# Fuse.net
KiCad netlist of a schematic drawn in Altium Designer
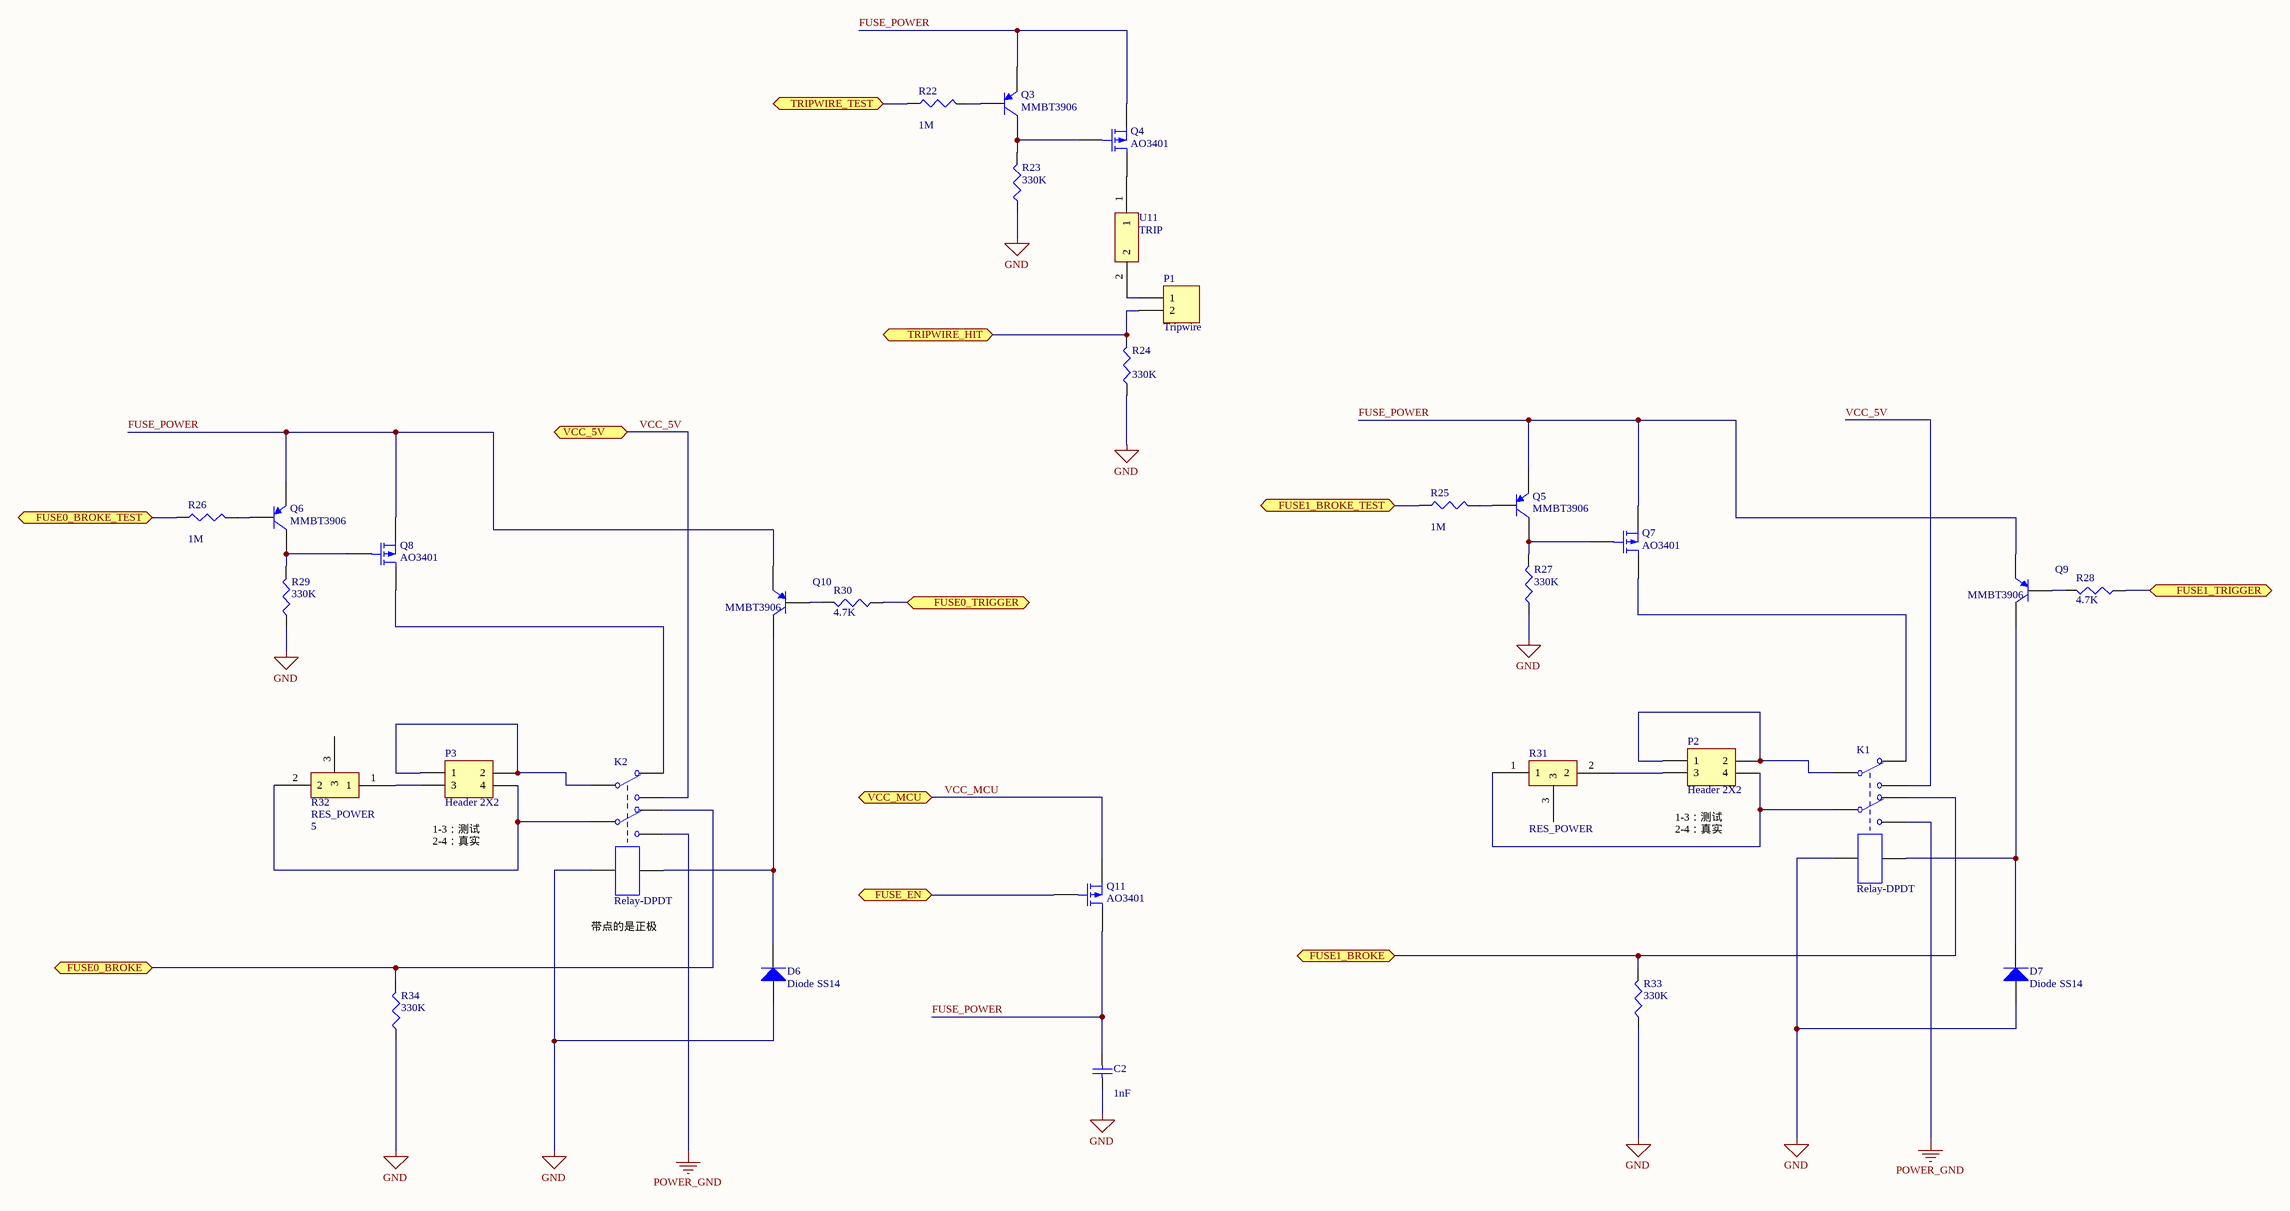
[diagram p0: Fuse.SchDoc]

(export (version "E")
  (design (tool "Eeschema 10.0.6"))
  (components
    (comp (ref "C2")
      (value "1nF")
      (footprint "clock:0603")
      (description "Capacitor (Semiconductor SIM Model)")
      (fields (field (name "Comment") "Cap Semi") (field (name "PUBLISHER") "Altium Limited"))
      (libsource (lib "Miscellaneous Devices") (part "Cap Semi"))
    )
    (comp (ref "D6")
      (value "Diode SS14")
      (footprint "clock:SMA")
      (description "1 Amp General Purpose Rectifier")
      (fields (field (name "PUBLISHER") "Altium Limited"))
      (libsource (lib "Miscellaneous Devices") (part "Diode 1N4005"))
    )
    (comp (ref "D7")
      (value "Diode SS14")
      (footprint "clock:SMA")
      (description "1 Amp General Purpose Rectifier")
      (fields (field (name "PUBLISHER") "Altium Limited"))
      (libsource (lib "Miscellaneous Devices") (part "Diode 1N4005"))
    )
    (comp (ref "K1")
      (value "Relay-DPDT")
      (footprint "clock:G6K2PY")
      (description "Dual-Pole Dual-Throw Relay")
      (fields (field (name "PUBLISHER") "Altium Limited"))
      (libsource (lib "Miscellaneous Devices") (part "Relay-DPDT"))
    )
    (comp (ref "K2")
      (value "Relay-DPDT")
      (footprint "clock:G6K2PY")
      (description "Dual-Pole Dual-Throw Relay")
      (fields (field (name "PUBLISHER") "Altium Limited"))
      (libsource (lib "Miscellaneous Devices") (part "Relay-DPDT"))
    )
    (comp (ref "P1")
      (value "Tripwire")
      (footprint "HDR1X2")
      (description "Header, 2-Pin")
      (fields (field (name "PUBLISHER") "Altium Limited"))
      (libsource (lib "Miscellaneous Connectors") (part "Header 2"))
    )
    (comp (ref "P2")
      (value "Header 2X2")
      (footprint "clock:HDR2X2")
      (description "Header, 2-Pin, Dual row")
      (fields (field (name "PUBLISHER") "Altium Limited"))
      (libsource (lib "Miscellaneous Connectors") (part "Header 2X2"))
    )
    (comp (ref "P3")
      (value "Header 2X2")
      (footprint "clock:HDR2X2")
      (description "Header, 2-Pin, Dual row")
      (fields (field (name "PUBLISHER") "Altium Limited"))
      (libsource (lib "Miscellaneous Connectors") (part "Header 2X2"))
    )
    (comp (ref "Q3")
      (value "MMBT3906")
      (footprint "clock:SOT23-3-PNP")
      (description "PNP Bipolar Transistor")
      (fields (field (name "PUBLISHER") "Altium Limited"))
      (libsource (lib "Miscellaneous Devices") (part "PNP"))
    )
    (comp (ref "Q4")
      (value "AO3401")
      (footprint "clock:SOT23-3-PMOS")
      (description "P-Channel MOSFET")
      (fields (field (name "PUBLISHER") "Altium Limited"))
      (libsource (lib "Miscellaneous Devices") (part "MOSFET-P"))
    )
    (comp (ref "Q5")
      (value "MMBT3906")
      (footprint "clock:SOT23-3-PNP")
      (description "PNP Bipolar Transistor")
      (fields (field (name "PUBLISHER") "Altium Limited"))
      (libsource (lib "Miscellaneous Devices") (part "PNP"))
    )
    (comp (ref "Q6")
      (value "MMBT3906")
      (footprint "clock:SOT23-3-PNP")
      (description "PNP Bipolar Transistor")
      (fields (field (name "PUBLISHER") "Altium Limited"))
      (libsource (lib "Miscellaneous Devices") (part "PNP"))
    )
    (comp (ref "Q7")
      (value "AO3401")
      (footprint "clock:SOT23-3-PMOS")
      (description "P-Channel MOSFET")
      (fields (field (name "PUBLISHER") "Altium Limited"))
      (libsource (lib "Miscellaneous Devices") (part "MOSFET-P"))
    )
    (comp (ref "Q8")
      (value "AO3401")
      (footprint "clock:SOT23-3-PMOS")
      (description "P-Channel MOSFET")
      (fields (field (name "PUBLISHER") "Altium Limited"))
      (libsource (lib "Miscellaneous Devices") (part "MOSFET-P"))
    )
    (comp (ref "Q9")
      (value "MMBT3906")
      (footprint "clock:SOT23-3-PNP")
      (description "PNP Bipolar Transistor")
      (fields (field (name "PUBLISHER") "Altium Limited"))
      (libsource (lib "Miscellaneous Devices") (part "PNP"))
    )
    (comp (ref "Q10")
      (value "MMBT3906")
      (footprint "clock:SOT23-3-PNP")
      (description "PNP Bipolar Transistor")
      (fields (field (name "PUBLISHER") "Altium Limited"))
      (libsource (lib "Miscellaneous Devices") (part "PNP"))
    )
    (comp (ref "Q11")
      (value "AO3401")
      (footprint "clock:SOT23-3-PMOS")
      (description "P-Channel MOSFET")
      (fields (field (name "PUBLISHER") "Altium Limited"))
      (libsource (lib "Miscellaneous Devices") (part "MOSFET-P"))
    )
    (comp (ref "R22")
      (value "1M")
      (footprint "clock:0603")
      (description "Resistor")
      (fields (field (name "Comment") "Res3") (field (name "PUBLISHER") "Altium Limited"))
      (libsource (lib "Miscellaneous Devices") (part "Res3"))
    )
    (comp (ref "R23")
      (value "330K")
      (footprint "clock:0603")
      (description "Resistor")
      (fields (field (name "Comment") "Res3") (field (name "PUBLISHER") "Altium Limited"))
      (libsource (lib "Miscellaneous Devices") (part "Res3"))
    )
    (comp (ref "R24")
      (value "330K")
      (footprint "clock:0603")
      (description "Resistor")
      (fields (field (name "Comment") "Res3") (field (name "PUBLISHER") "Altium Limited"))
      (libsource (lib "Miscellaneous Devices") (part "Res3"))
    )
    (comp (ref "R25")
      (value "1M")
      (footprint "clock:0603")
      (description "Resistor")
      (fields (field (name "Comment") "Res3") (field (name "PUBLISHER") "Altium Limited"))
      (libsource (lib "Miscellaneous Devices") (part "Res3"))
    )
    (comp (ref "R26")
      (value "1M")
      (footprint "clock:0603")
      (description "Resistor")
      (fields (field (name "Comment") "Res3") (field (name "PUBLISHER") "Altium Limited"))
      (libsource (lib "Miscellaneous Devices") (part "Res3"))
    )
    (comp (ref "R27")
      (value "330K")
      (footprint "clock:0603")
      (description "Resistor")
      (fields (field (name "Comment") "Res3") (field (name "PUBLISHER") "Altium Limited"))
      (libsource (lib "Miscellaneous Devices") (part "Res3"))
    )
    (comp (ref "R28")
      (value "4.7K")
      (footprint "clock:0603")
      (description "Resistor")
      (fields (field (name "Comment") "Res3") (field (name "PUBLISHER") "Altium Limited"))
      (libsource (lib "Miscellaneous Devices") (part "Res3"))
    )
    (comp (ref "R29")
      (value "330K")
      (footprint "clock:0603")
      (description "Resistor")
      (fields (field (name "Comment") "Res3") (field (name "PUBLISHER") "Altium Limited"))
      (libsource (lib "Miscellaneous Devices") (part "Res3"))
    )
    (comp (ref "R30")
      (value "4.7K")
      (footprint "clock:0603")
      (description "Resistor")
      (fields (field (name "Comment") "Res3") (field (name "PUBLISHER") "Altium Limited"))
      (libsource (lib "Miscellaneous Devices") (part "Res3"))
    )
    (comp (ref "R31")
      (value "RES_POWER")
      (footprint "clock:RES_POWER")
      (libsource (lib "clock") (part "RES_POWER"))
    )
    (comp (ref "R32")
      (value "RES_POWER")
      (footprint "clock:RES_POWER")
      (fields (field (name "ALTIUM_VALUE") "5"))
      (libsource (lib "") (part "RES_POWER_1"))
    )
    (comp (ref "R33")
      (value "330K")
      (footprint "clock:0603")
      (description "Resistor")
      (fields (field (name "Comment") "Res3") (field (name "PUBLISHER") "Altium Limited"))
      (libsource (lib "Miscellaneous Devices") (part "Res3"))
    )
    (comp (ref "R34")
      (value "330K")
      (footprint "clock:0603")
      (description "Resistor")
      (fields (field (name "Comment") "Res3") (field (name "PUBLISHER") "Altium Limited"))
      (libsource (lib "Miscellaneous Devices") (part "Res3"))
    )
    (comp (ref "U11") (value "TRIP") (footprint "clock:TRIP") (libsource (lib "clock") (part "TRIP")))
  )
  (nets
    (net (code "1") (name "/FUSE0_BROKE") (class "Default")
      (node (ref "K2") (pin "5") (pinfunction "5_5") (pintype "passive"))
      (node (ref "R34") (pin "2") (pinfunction "2_2") (pintype "passive"))
    )
    (net (code "2") (name "/FUSE0_BROKE_TEST") (class "Default")
      (node (ref "R26") (pin "1") (pinfunction "1_1") (pintype "passive"))
    )
    (net (code "3") (name "/FUSE0_TRIGGER") (class "Default")
      (node (ref "R30") (pin "1") (pinfunction "1_1") (pintype "passive"))
    )
    (net (code "4") (name "/FUSE1_BROKE") (class "Default")
      (node (ref "K1") (pin "5") (pinfunction "5_5") (pintype "passive"))
      (node (ref "R33") (pin "2") (pinfunction "2_2") (pintype "passive"))
    )
    (net (code "5") (name "/FUSE1_BROKE_TEST") (class "Default")
      (node (ref "R25") (pin "1") (pinfunction "1_1") (pintype "passive"))
    )
    (net (code "6") (name "/FUSE1_TRIGGER") (class "Default")
      (node (ref "R28") (pin "1") (pinfunction "1_1") (pintype "passive"))
    )
    (net (code "7") (name "/FUSE_EN") (class "Default")
      (node (ref "Q11") (pin "2") (pinfunction "G_2") (pintype "passive"))
    )
    (net (code "8") (name "/FUSE_POWER") (class "Default")
      (node (ref "C2") (pin "2") (pinfunction "2_2") (pintype "passive"))
      (node (ref "Q10") (pin "3") (pinfunction "E_3") (pintype "passive"))
      (node (ref "Q11") (pin "1") (pinfunction "D_1") (pintype "passive"))
      (node (ref "Q3") (pin "3") (pinfunction "E_3") (pintype "passive"))
      (node (ref "Q4") (pin "3") (pinfunction "S_3") (pintype "passive"))
      (node (ref "Q5") (pin "3") (pinfunction "E_3") (pintype "passive"))
      (node (ref "Q6") (pin "3") (pinfunction "E_3") (pintype "passive"))
      (node (ref "Q7") (pin "3") (pinfunction "S_3") (pintype "passive"))
      (node (ref "Q8") (pin "3") (pinfunction "S_3") (pintype "passive"))
      (node (ref "Q9") (pin "3") (pinfunction "E_3") (pintype "passive"))
    )
    (net (code "9") (name "/TRIPWIRE_HIT") (class "Default")
      (node (ref "P1") (pin "2") (pinfunction "2_2") (pintype "passive"))
      (node (ref "R24") (pin "2") (pinfunction "2_2") (pintype "passive"))
    )
    (net (code "10") (name "/TRIPWIRE_TEST") (class "Default")
      (node (ref "R22") (pin "1") (pinfunction "1_1") (pintype "passive"))
    )
    (net (code "11") (name "/VCC_5V") (class "Default")
      (node (ref "K1") (pin "3") (pinfunction "3_3") (pintype "passive"))
      (node (ref "K2") (pin "3") (pinfunction "3_3") (pintype "passive"))
    )
    (net (code "12") (name "/VCC_MCU") (class "Default")
      (node (ref "Q11") (pin "3") (pinfunction "S_3") (pintype "passive"))
    )
    (net (code "13") (name "GND") (class "Default")
      (node (ref "C2") (pin "1") (pinfunction "1_1") (pintype "passive"))
      (node (ref "D6") (pin "1") (pinfunction "A_1") (pintype "passive"))
      (node (ref "D7") (pin "1") (pinfunction "A_1") (pintype "passive"))
      (node (ref "K1") (pin "7") (pinfunction "7_7") (pintype "passive"))
      (node (ref "K2") (pin "7") (pinfunction "7_7") (pintype "passive"))
      (node (ref "R23") (pin "1") (pinfunction "1_1") (pintype "passive"))
      (node (ref "R24") (pin "1") (pinfunction "1_1") (pintype "passive"))
      (node (ref "R27") (pin "1") (pinfunction "1_1") (pintype "passive"))
      (node (ref "R29") (pin "1") (pinfunction "1_1") (pintype "passive"))
      (node (ref "R33") (pin "1") (pinfunction "1_1") (pintype "passive"))
      (node (ref "R34") (pin "1") (pinfunction "1_1") (pintype "passive"))
    )
    (net (code "14") (name "Net-(D6-K)") (class "Default")
      (node (ref "D6") (pin "2") (pinfunction "K_2") (pintype "passive"))
      (node (ref "K2") (pin "8") (pinfunction "8_8") (pintype "passive"))
      (node (ref "Q10") (pin "1") (pinfunction "C_1") (pintype "passive"))
    )
    (net (code "15") (name "Net-(D7-K)") (class "Default")
      (node (ref "D7") (pin "2") (pinfunction "K_2") (pintype "passive"))
      (node (ref "K1") (pin "8") (pinfunction "8_8") (pintype "passive"))
      (node (ref "Q9") (pin "1") (pinfunction "C_1") (pintype "passive"))
    )
    (net (code "16") (name "Net-(K1-Pad1)") (class "Default")
      (node (ref "K1") (pin "1") (pinfunction "1_1") (pintype "passive"))
      (node (ref "P2") (pin "1") (pinfunction "1_1") (pintype "passive"))
      (node (ref "P2") (pin "2") (pinfunction "2_2") (pintype "passive"))
    )
    (net (code "17") (name "Net-(K1-Pad4)") (class "Default")
      (node (ref "K1") (pin "4") (pinfunction "4_4") (pintype "passive"))
      (node (ref "P2") (pin "4") (pinfunction "4_4") (pintype "passive"))
      (node (ref "R31") (pin "1") (pinfunction "1_1") (pintype "passive"))
    )
    (net (code "18") (name "Net-(K2-Pad1)") (class "Default")
      (node (ref "K2") (pin "1") (pinfunction "1_1") (pintype "passive"))
      (node (ref "P3") (pin "1") (pinfunction "1_1") (pintype "passive"))
      (node (ref "P3") (pin "2") (pinfunction "2_2") (pintype "passive"))
    )
    (net (code "19") (name "Net-(K2-Pad4)") (class "Default")
      (node (ref "K2") (pin "4") (pinfunction "4_4") (pintype "passive"))
      (node (ref "P3") (pin "4") (pinfunction "4_4") (pintype "passive"))
      (node (ref "R32") (pin "2") (pinfunction "2_2") (pintype "passive"))
    )
    (net (code "20") (name "Net-(P1-Pad1)") (class "Default")
      (node (ref "P1") (pin "1") (pinfunction "1_1") (pintype "passive"))
      (node (ref "U11") (pin "2") (pinfunction "2_2") (pintype "passive"))
    )
    (net (code "21") (name "Net-(P2-Pad3)") (class "Default")
      (node (ref "P2") (pin "3") (pinfunction "3_3") (pintype "passive"))
      (node (ref "R31") (pin "2") (pinfunction "2_2") (pintype "passive"))
    )
    (net (code "22") (name "Net-(P3-Pad3)") (class "Default")
      (node (ref "P3") (pin "3") (pinfunction "3_3") (pintype "passive"))
      (node (ref "R32") (pin "1") (pinfunction "1_1") (pintype "passive"))
    )
    (net (code "23") (name "Net-(Q3-B)") (class "Default")
      (node (ref "Q3") (pin "2") (pinfunction "B_2") (pintype "passive"))
      (node (ref "R22") (pin "2") (pinfunction "2_2") (pintype "passive"))
    )
    (net (code "24") (name "Net-(Q3-C)") (class "Default")
      (node (ref "Q3") (pin "1") (pinfunction "C_1") (pintype "passive"))
      (node (ref "Q4") (pin "2") (pinfunction "G_2") (pintype "passive"))
      (node (ref "R23") (pin "2") (pinfunction "2_2") (pintype "passive"))
    )
    (net (code "25") (name "Net-(Q4-D)") (class "Default")
      (node (ref "Q4") (pin "1") (pinfunction "D_1") (pintype "passive"))
      (node (ref "U11") (pin "1") (pinfunction "1_1") (pintype "passive"))
    )
    (net (code "26") (name "Net-(Q5-B)") (class "Default")
      (node (ref "Q5") (pin "2") (pinfunction "B_2") (pintype "passive"))
      (node (ref "R25") (pin "2") (pinfunction "2_2") (pintype "passive"))
    )
    (net (code "27") (name "Net-(Q5-C)") (class "Default")
      (node (ref "Q5") (pin "1") (pinfunction "C_1") (pintype "passive"))
      (node (ref "Q7") (pin "2") (pinfunction "G_2") (pintype "passive"))
      (node (ref "R27") (pin "2") (pinfunction "2_2") (pintype "passive"))
    )
    (net (code "28") (name "Net-(Q6-B)") (class "Default")
      (node (ref "Q6") (pin "2") (pinfunction "B_2") (pintype "passive"))
      (node (ref "R26") (pin "2") (pinfunction "2_2") (pintype "passive"))
    )
    (net (code "29") (name "Net-(Q6-C)") (class "Default")
      (node (ref "Q6") (pin "1") (pinfunction "C_1") (pintype "passive"))
      (node (ref "Q8") (pin "2") (pinfunction "G_2") (pintype "passive"))
      (node (ref "R29") (pin "2") (pinfunction "2_2") (pintype "passive"))
    )
    (net (code "30") (name "Net-(Q7-D)") (class "Default")
      (node (ref "K1") (pin "2") (pinfunction "2_2") (pintype "passive"))
      (node (ref "Q7") (pin "1") (pinfunction "D_1") (pintype "passive"))
    )
    (net (code "31") (name "Net-(Q8-D)") (class "Default")
      (node (ref "K2") (pin "2") (pinfunction "2_2") (pintype "passive"))
      (node (ref "Q8") (pin "1") (pinfunction "D_1") (pintype "passive"))
    )
    (net (code "32") (name "Net-(Q9-B)") (class "Default")
      (node (ref "Q9") (pin "2") (pinfunction "B_2") (pintype "passive"))
      (node (ref "R28") (pin "2") (pinfunction "2_2") (pintype "passive"))
    )
    (net (code "33") (name "Net-(Q10-B)") (class "Default")
      (node (ref "Q10") (pin "2") (pinfunction "B_2") (pintype "passive"))
      (node (ref "R30") (pin "2") (pinfunction "2_2") (pintype "passive"))
    )
    (net (code "34") (name "POWER_GND") (class "Default")
      (node (ref "K1") (pin "6") (pinfunction "6_6") (pintype "passive"))
      (node (ref "K2") (pin "6") (pinfunction "6_6") (pintype "passive"))
    )
    (net (code "35") (name "unconnected-(R31-Pad3)") (class "Default")
      (node (ref "R31") (pin "3") (pinfunction "3_3") (pintype "passive"))
    )
    (net (code "36") (name "unconnected-(R32-Pad3)") (class "Default")
      (node (ref "R32") (pin "3") (pinfunction "3_3") (pintype "passive"))
    )
  )
)
